# RTC.net
KiCad netlist of a schematic drawn in Altium Designer
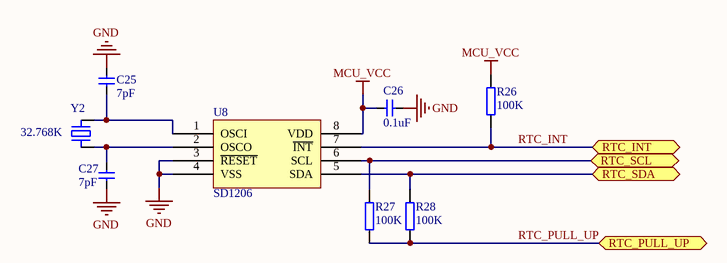
[diagram p0: RTC.SchDoc]

(export (version "E")
  (design (tool "Eeschema 10.0.6"))
  (components
    (comp (ref "C25") (value "7pF") (footprint "0603C") (libsource (lib "dtu02") (part "CAP")))
    (comp (ref "C26") (value "0.1uF") (footprint "0603C") (libsource (lib "dtu02") (part "CAP")))
    (comp (ref "C27") (value "7pF") (footprint "0603C") (libsource (lib "dtu02") (part "CAP")))
    (comp (ref "R26") (value "100K") (footprint "0603R") (libsource (lib "dtu02") (part "RES2A")))
    (comp (ref "R27") (value "100K") (footprint "0603R") (libsource (lib "dtu02") (part "RES2A")))
    (comp (ref "R28") (value "100K") (footprint "0603R") (libsource (lib "dtu02") (part "RES2A")))
    (comp (ref "U8") (value "SD1206") (footprint "SOP8") (libsource (lib "dtu02") (part "PCF8593")))
    (comp (ref "Y2")
      (value "32.768K")
      (footprint "3215SMD")
      (description "无源贴片晶振 3215 2脚  FC-135")
      (libsource (lib "G-BOX") (part "CRYSTAL_2P"))
    )
  )
  (nets
    (net (code "1") (name "/RTC_INT") (class "Default")
      (node (ref "R26") (pin "1") (pintype "passive"))
      (node (ref "U8") (pin "7") (pinfunction "~{INT}_7") (pintype "passive"))
    )
    (net (code "2") (name "/RTC_PULL_UP") (class "Default")
      (node (ref "R27") (pin "1") (pintype "passive"))
      (node (ref "R28") (pin "1") (pintype "passive"))
    )
    (net (code "3") (name "/RTC_SCL") (class "Default")
      (node (ref "R27") (pin "2") (pintype "passive"))
      (node (ref "U8") (pin "6") (pinfunction "SCL_6") (pintype "passive"))
    )
    (net (code "4") (name "/RTC_SDA") (class "Default")
      (node (ref "R28") (pin "2") (pintype "passive"))
      (node (ref "U8") (pin "5") (pinfunction "SDA_5") (pintype "passive"))
    )
    (net (code "5") (name "GND") (class "Default")
      (node (ref "C25") (pin "1") (pintype "passive"))
      (node (ref "C26") (pin "2") (pintype "passive"))
      (node (ref "C27") (pin "1") (pintype "passive"))
      (node (ref "U8") (pin "3") (pinfunction "~{RESET}_3") (pintype "passive"))
      (node (ref "U8") (pin "4") (pinfunction "VSS_4") (pintype "passive"))
    )
    (net (code "6") (name "MCU_VCC") (class "Default")
      (node (ref "C26") (pin "1") (pintype "passive"))
      (node (ref "R26") (pin "2") (pintype "passive"))
      (node (ref "U8") (pin "8") (pinfunction "VDD_8") (pintype "passive"))
    )
    (net (code "7") (name "Net-(U8-OSCI)") (class "Default")
      (node (ref "C25") (pin "2") (pintype "passive"))
      (node (ref "U8") (pin "1") (pinfunction "OSCI_1") (pintype "passive"))
      (node (ref "Y2") (pin "1") (pintype "passive"))
    )
    (net (code "8") (name "Net-(U8-OSCO)") (class "Default")
      (node (ref "C27") (pin "2") (pintype "passive"))
      (node (ref "U8") (pin "2") (pinfunction "OSCO_2") (pintype "passive"))
      (node (ref "Y2") (pin "2") (pintype "passive"))
    )
  )
)
